# Supply_15V.net
KiCad netlist of a schematic drawn in Altium Designer
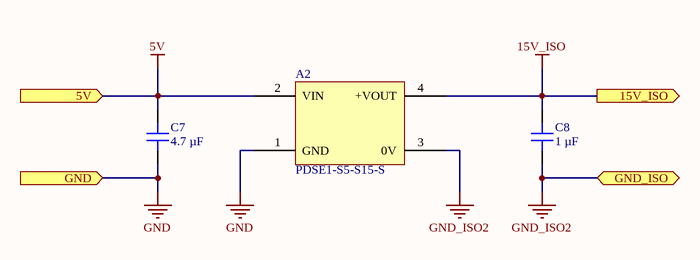
[diagram p0: Supply 15V.SchDoc]

(export (version "E")
  (design (tool "Eeschema 10.0.6"))
  (components
    (comp (ref "A2")
      (value "PDSE1-S5-S15-S")
      (footprint "CUI PDSE1-S")
      (description "DC DC CONVERTER 15V 1W")
      (fields (field (name "MANUFACTURER") "CUI Inc."))
      (libsource (lib "altiumlibrary.com") (part "CUI PDSE1-S"))
    )
    (comp (ref "C7")
      (value "4.7 µF")
      (footprint "CAP 0805_2012")
      (description "CAP CER 4.7UF 25V X7R 0805")
      (fields
        (field (name "PART NUMBER") "CL21B475KAFNNNE")
        (field (name "MANUFACTURER") "Samsung Electro-Mechanics")
      )
      (libsource (lib "altiumlibrary.com") (part "Capacitor"))
    )
    (comp (ref "C8")
      (value "1 µF")
      (footprint "CAP 0805_2012")
      (description "CAP CER 1UF 50V X7R 0805")
      (fields
        (field (name "PART NUMBER") "GCJ21BR71H105KA01L")
        (field (name "MANUFACTURER") "Murata Electronics")
      )
      (libsource (lib "altiumlibrary.com") (part "Capacitor"))
    )
  )
  (nets
    (net (code "1") (name "5V") (class "Default")
      (node (ref "A2") (pin "2") (pinfunction "VIN_2") (pintype "passive"))
      (node (ref "C7") (pin "2") (pinfunction "2_2") (pintype "passive"))
    )
    (net (code "2") (name "15V_ISO") (class "Default")
      (node (ref "A2") (pin "4") (pinfunction "+VOUT_4") (pintype "passive"))
      (node (ref "C8") (pin "2") (pinfunction "2_2") (pintype "passive"))
    )
    (net (code "3") (name "GND") (class "Default")
      (node (ref "A2") (pin "1") (pinfunction "GND_1") (pintype "passive"))
      (node (ref "C7") (pin "1") (pinfunction "1_1") (pintype "passive"))
    )
    (net (code "4") (name "GND_ISO2") (class "Default")
      (node (ref "A2") (pin "3") (pinfunction "0V_3") (pintype "passive"))
      (node (ref "C8") (pin "1") (pinfunction "1_1") (pintype "passive"))
    )
  )
)
